# TopLevelBlock.net
KiCad netlist of a schematic drawn in Altium Designer
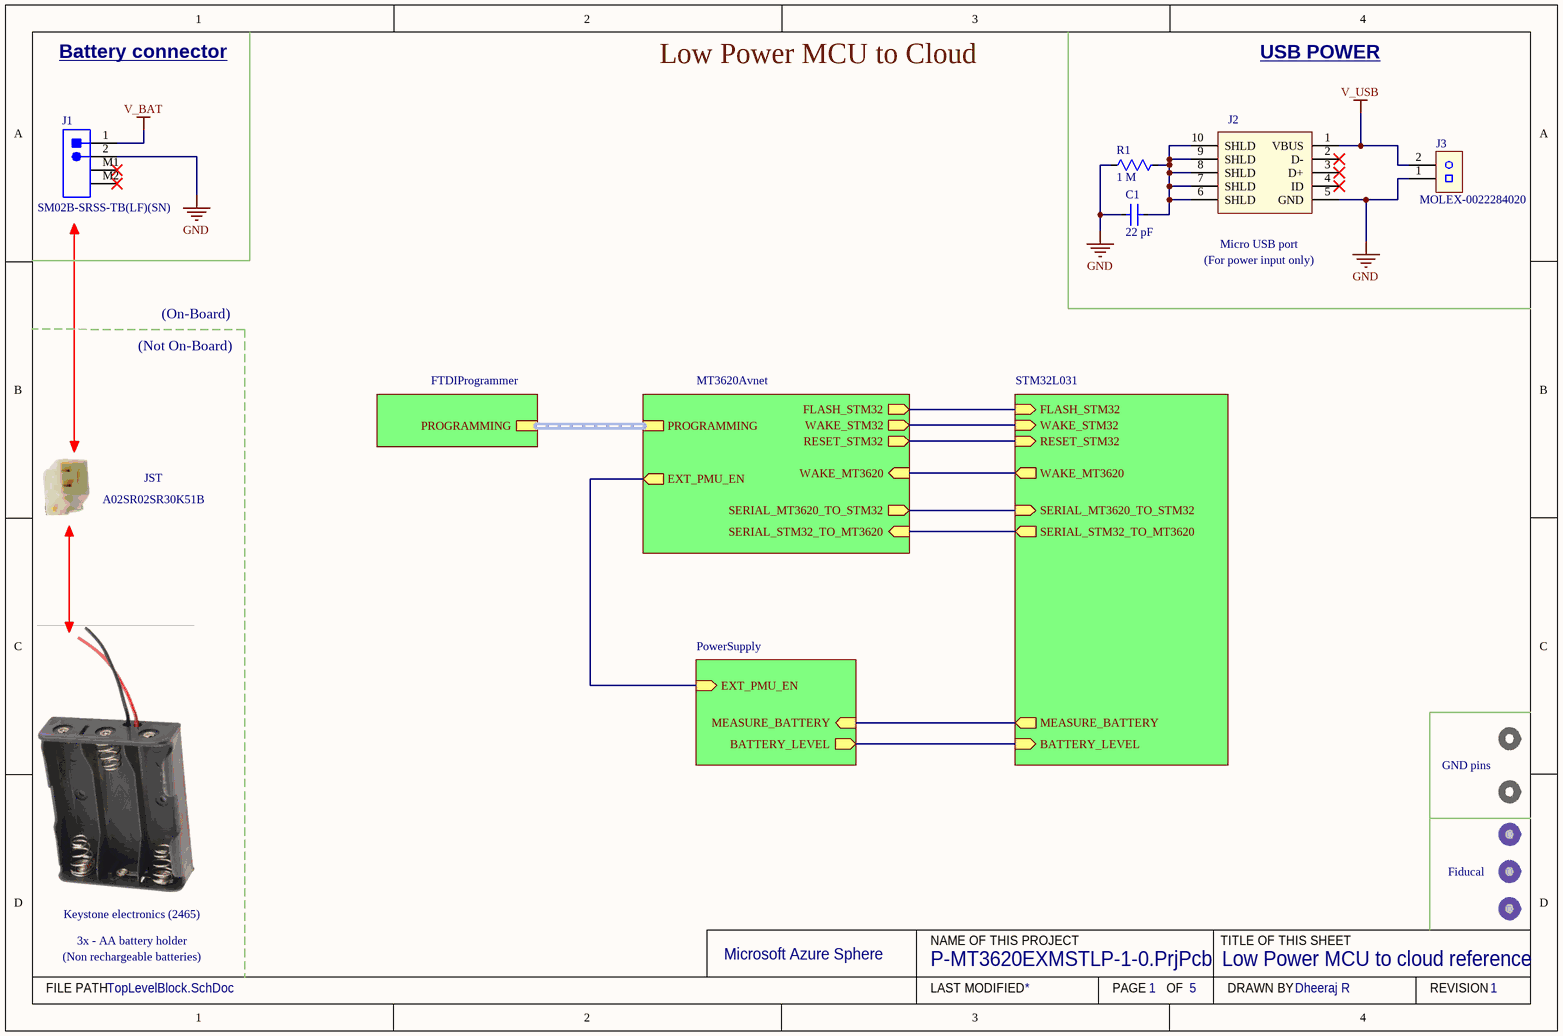
[diagram p0: TopLevelBlock.SchDoc]

(export (version "E")
  (design (tool "Eeschema 10.0.6"))
  (components
    (comp (ref "C1")
      (value "22 pF")
      (footprint "CC0603")
      (description "22PF 0603 100V C0G/NPO")
      (fields
        (field (name "MANUFACTURER") "Yageo")
        (field (name "MANUFACTURER PART NUMBER") "CC0603JRNPO0BN220")
      )
      (libsource (lib "Yageo") (part "CC0603JRNPO0BN220"))
    )
    (comp (ref "J1")
      (value "SM02B-SRSS-TB(LF)(SN)")
      (footprint "SM02B-SRSS-TB")
      (description "Conn Shrouded Header HDR 2 POS 1mm Solder RA SMD T/R")
      (fields (field (name "MANUFACTURER") "JST"))
      (libsource (lib "JST") (part "SM02B-SRSS-TB(LF)(SN)"))
    )
    (comp (ref "J2")
      (value "USB Micro-B")
      (footprint "MOLEX-1050170001")
      (description "Micro; B Type; receptacle; Bottom Mount, SMT, with Solder Tabs, Lead-Free")
      (fields (field (name "MANUFACTURER") "Molex") (field (name "MANUFACTURER PART NUMBER") "1050170001"))
      (libsource (lib "Molex") (part "MOLEX-1050170001"))
    )
    (comp (ref "J3")
      (value "MOLEX-0022284020")
      (footprint "0022284020")
      (description "CONN HEADER 2POS .100 VERT TIN")
      (fields
        (field (name "MANUFACTURER") "Molex, LLC")
        (field (name "MANUFACTURER PART NUMBER") "0022284020")
      )
      (libsource (lib "Molex") (part "MOLEX-0022284020"))
    )
    (comp (ref "R1")
      (value "1 M")
      (footprint "RC0603")
      (description "1M 0603 Case 1% 0.1W 100ppm/C")
      (fields
        (field (name "MANUFACTURER") "Yageo")
        (field (name "MANUFACTURER PART NUMBER") "RC0603FR-071ML")
      )
      (libsource (lib "Yageo") (part "RC0603FR-071ML"))
    )
  )
  (nets
    (net (code "11") (name "GND") (class "Default")
      (node (ref "C1") (pin "1") (pinfunction "1_1") (pintype "passive"))
      (node (ref "J1") (pin "2") (pinfunction "2_2") (pintype "passive"))
      (node (ref "J2") (pin "5") (pinfunction "GND_5") (pintype "passive"))
      (node (ref "J3") (pin "1") (pinfunction "1_1") (pintype "passive"))
      (node (ref "R1") (pin "2") (pinfunction "2_2") (pintype "passive"))
    )
    (net (code "12") (name "Net-(C1-Pad2)") (class "Default")
      (node (ref "C1") (pin "2") (pinfunction "2_2") (pintype "passive"))
      (node (ref "J2") (pin "10") (pinfunction "SHLD_10") (pintype "passive"))
      (node (ref "J2") (pin "6") (pinfunction "SHLD_6") (pintype "passive"))
      (node (ref "J2") (pin "7") (pinfunction "SHLD_7") (pintype "passive"))
      (node (ref "J2") (pin "8") (pinfunction "SHLD_8") (pintype "passive"))
      (node (ref "J2") (pin "9") (pinfunction "SHLD_9") (pintype "passive"))
      (node (ref "R1") (pin "1") (pinfunction "1_1") (pintype "passive"))
    )
    (net (code "13") (name "V_BAT") (class "Default")
      (node (ref "J1") (pin "1") (pinfunction "1_1") (pintype "passive"))
    )
    (net (code "14") (name "V_USB") (class "Default")
      (node (ref "J2") (pin "1") (pinfunction "VBUS_1") (pintype "passive"))
      (node (ref "J3") (pin "2") (pinfunction "2_2") (pintype "passive"))
    )
    (net (code "15") (name "unconnected-(J1-PadM1)") (class "Default")
      (node (ref "J1") (pin "M1") (pinfunction "M1_M1") (pintype "passive+no_connect"))
    )
    (net (code "16") (name "unconnected-(J1-PadM2)") (class "Default")
      (node (ref "J1") (pin "M2") (pinfunction "M2_M2") (pintype "passive+no_connect"))
    )
    (net (code "17") (name "unconnected-(J2-D+-Pad3)") (class "Default")
      (node (ref "J2") (pin "3") (pinfunction "D+_3") (pintype "passive+no_connect"))
    )
    (net (code "18") (name "unconnected-(J2-D--Pad2)") (class "Default")
      (node (ref "J2") (pin "2") (pinfunction "D-_2") (pintype "passive+no_connect"))
    )
    (net (code "19") (name "unconnected-(J2-ID-Pad4)") (class "Default")
      (node (ref "J2") (pin "4") (pinfunction "ID_4") (pintype "passive+no_connect"))
    )
  )
)
